# 05_USB.net
KiCad netlist of a schematic drawn in Altium Designer
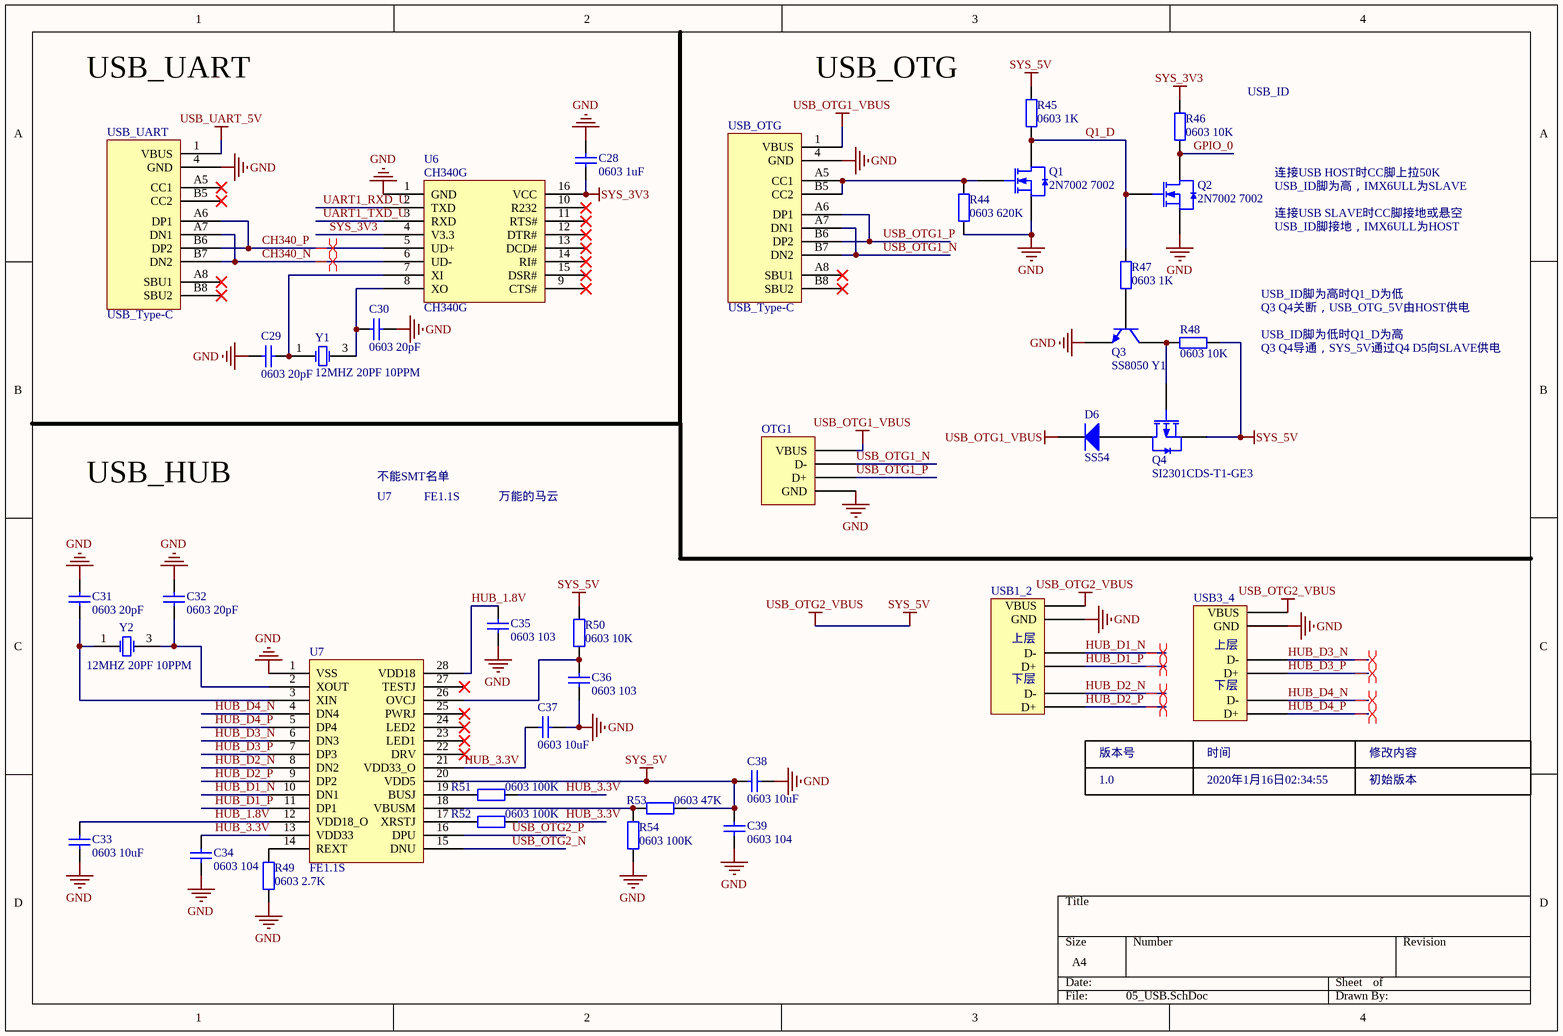
[diagram p0: 05_USB.SchDoc]

(export (version "E")
  (design (tool "Eeschema 10.0.6"))
  (components
    (comp (ref "C28")
      (value "0603 1uF")
      (footprint "LC-0603_C")
      (description "贴片电容")
      (libsource (lib "JLC") (part "0603 1.5nF (152) 10% 50V"))
    )
    (comp (ref "C29")
      (value "0603 20pF")
      (footprint "LC-0603_C")
      (description "贴片电容")
      (libsource (lib "JLC") (part "0603 1.5nF (152) 10% 50V"))
    )
    (comp (ref "C30")
      (value "0603 20pF")
      (footprint "LC-0603_C")
      (description "贴片电容")
      (libsource (lib "JLC") (part "0603 1.5nF (152) 10% 50V"))
    )
    (comp (ref "C31")
      (value "0603 20pF")
      (footprint "LC-0603_C")
      (description "贴片电容")
      (libsource (lib "JLC") (part "0603 1.5nF (152) 10% 50V"))
    )
    (comp (ref "C32")
      (value "0603 20pF")
      (footprint "LC-0603_C")
      (description "贴片电容")
      (libsource (lib "JLC") (part "0603 1.5nF (152) 10% 50V"))
    )
    (comp (ref "C33")
      (value "0603 10uF")
      (footprint "LC-0603_C")
      (description "贴片电容")
      (libsource (lib "JLC") (part "0603 1.5nF (152) 10% 50V"))
    )
    (comp (ref "C34")
      (value "0603 104")
      (footprint "LC-0603_C")
      (description "贴片电容")
      (libsource (lib "JLC") (part "0603 1.5nF (152) 10% 50V"))
    )
    (comp (ref "C35")
      (value "0603 103")
      (footprint "LC-0603_C")
      (description "贴片电容")
      (libsource (lib "JLC") (part "0603 1.5nF (152) 10% 50V"))
    )
    (comp (ref "C36")
      (value "0603 103")
      (footprint "LC-0603_C")
      (description "贴片电容")
      (libsource (lib "JLC") (part "0603 1.5nF (152) 10% 50V"))
    )
    (comp (ref "C37")
      (value "0603 10uF")
      (footprint "LC-0603_C")
      (description "贴片电容")
      (libsource (lib "JLC") (part "0603 1.5nF (152) 10% 50V"))
    )
    (comp (ref "C38")
      (value "0603 10uF")
      (footprint "LC-0603_C")
      (description "贴片电容")
      (libsource (lib "JLC") (part "0603 1.5nF (152) 10% 50V"))
    )
    (comp (ref "C39")
      (value "0603 104")
      (footprint "LC-0603_C")
      (description "贴片电容")
      (libsource (lib "JLC") (part "0603 1.5nF (152) 10% 50V"))
    )
    (comp (ref "D6")
      (value "SS54")
      (footprint "LC-SMA(DO-214AC)_S1")
      (description "二极管")
      (libsource (lib "JLC") (part "SMA(DO-214AC) SS54"))
    )
    (comp (ref "OTG1")
      (value "~")
      (footprint "USB插座_侧插")
      (libsource (lib "Integrated_Library2") (part "USB_插座"))
    )
    (comp (ref "Q1")
      (value "2N7002 7002")
      (footprint "LC-SOT-23(SOT-23-3)")
      (description "MOS(场效应管)")
      (libsource (lib "JLC") (part "2N7002 7002"))
    )
    (comp (ref "Q2")
      (value "2N7002 7002")
      (footprint "LC-SOT-23(SOT-23-3)")
      (description "MOS(场效应管)")
      (libsource (lib "JLC") (part "2N7002 7002"))
    )
    (comp (ref "Q3")
      (value "SS8050 Y1")
      (footprint "LC-SOT-23(SOT-23-3)")
      (description "三极管")
      (libsource (lib "JLC") (part "SOT-23 SS8050 Y1"))
    )
    (comp (ref "Q4")
      (value "SI2301CDS-T1-GE3")
      (footprint "LC-SOT-23(SOT-23-3)")
      (description "MOS(场效应管)")
      (libsource (lib "JLC") (part "SI2301CDS-T1-GE3"))
    )
    (comp (ref "R44")
      (value "0603 620K")
      (footprint "LC-0603_R")
      (description "贴片电阻")
      (libsource (lib "JLC") (part "0603 1.1KΩ (1101) 1%"))
    )
    (comp (ref "R45")
      (value "0603 1K")
      (footprint "LC-0603_R")
      (description "贴片电阻")
      (libsource (lib "JLC") (part "0603 1.1KΩ (1101) 1%"))
    )
    (comp (ref "R46")
      (value "0603 10K")
      (footprint "LC-0603_R")
      (description "贴片电阻")
      (libsource (lib "JLC") (part "0603 1.1KΩ (1101) 1%"))
    )
    (comp (ref "R47")
      (value "0603 1K")
      (footprint "LC-0603_R")
      (description "贴片电阻")
      (libsource (lib "JLC") (part "0603 1.1KΩ (1101) 1%"))
    )
    (comp (ref "R48")
      (value "0603 10K")
      (footprint "LC-0603_R")
      (description "贴片电阻")
      (libsource (lib "") (part "0603 1.1KΩ (1101) 1%_2"))
    )
    (comp (ref "R49")
      (value "0603 2.7K")
      (footprint "LC-0603_R")
      (description "贴片电阻")
      (libsource (lib "JLC") (part "0603 1.1KΩ (1101) 1%"))
    )
    (comp (ref "R50")
      (value "0603 10K")
      (footprint "LC-0603_R")
      (description "贴片电阻")
      (libsource (lib "JLC") (part "0603 1.1KΩ (1101) 1%"))
    )
    (comp (ref "R51")
      (value "0603 100K")
      (footprint "LC-0603_R")
      (description "贴片电阻")
      (libsource (lib "") (part "0603 1.1KΩ (1101) 1%_2"))
    )
    (comp (ref "R52")
      (value "0603 100K")
      (footprint "LC-0603_R")
      (description "贴片电阻")
      (libsource (lib "") (part "0603 1.1KΩ (1101) 1%_2"))
    )
    (comp (ref "R53")
      (value "0603 47K")
      (footprint "LC-0603_R")
      (description "贴片电阻")
      (libsource (lib "") (part "0603 1.1KΩ (1101) 1%_2"))
    )
    (comp (ref "R54")
      (value "0603 100K")
      (footprint "LC-0603_R")
      (description "贴片电阻")
      (libsource (lib "") (part "0603 1.1KΩ (1101) 1%_1"))
    )
    (comp (ref "U6")
      (value "CH340G")
      (footprint "LC-SOIC-16_150mil")
      (description "USB")
      (libsource (lib "JLC") (part "CH340G"))
    )
    (comp (ref "U7")
      (value "FE1.1S")
      (footprint "LC-SSOP-28_150mil")
      (libsource (lib "Integrated_Library2") (part "FE1.1S"))
    )
    (comp (ref "USB1_2")
      (value "~")
      (footprint "USB插座_双层")
      (libsource (lib "Integrated_Library2") (part "USB双层插座"))
    )
    (comp (ref "USB3_4")
      (value "~")
      (footprint "USB插座_双层")
      (libsource (lib "Integrated_Library2") (part "USB双层插座"))
    )
    (comp (ref "USB_OTG")
      (value "USB_Type-C")
      (footprint "Type-C 16P")
      (libsource (lib "Integrated_Library2") (part "USB_Type-C"))
    )
    (comp (ref "USB_UART")
      (value "USB_Type-C")
      (footprint "Type-C 16P")
      (libsource (lib "Integrated_Library2") (part "USB_Type-C"))
    )
    (comp (ref "Y1")
      (value "12MHZ 20PF 10PPM")
      (footprint "LC-SMD-3225_4P")
      (description "贴片晶振")
      (libsource (lib "JLC") (part "SMD-3225_4P  12MHZ 20PF 10PPM"))
    )
    (comp (ref "Y2")
      (value "12MHZ 20PF 10PPM")
      (footprint "LC-SMD-3225_4P")
      (description "贴片晶振")
      (libsource (lib "JLC") (part "SMD-3225_4P  12MHZ 20PF 10PPM"))
    )
  )
  (nets
    (net (code "1") (name "/CH340_N") (class "Default")
      (node (ref "U6") (pin "6") (pinfunction "UD-_6") (pintype "passive"))
      (node (ref "USB_UART") (pin "A7") (pinfunction "DN1_A7") (pintype "passive"))
      (node (ref "USB_UART") (pin "B7") (pinfunction "DN2_B7") (pintype "passive"))
    )
    (net (code "2") (name "/CH340_P") (class "Default")
      (node (ref "U6") (pin "5") (pinfunction "UD+_5") (pintype "passive"))
      (node (ref "USB_UART") (pin "A6") (pinfunction "DP1_A6") (pintype "passive"))
      (node (ref "USB_UART") (pin "B6") (pinfunction "DP2_B6") (pintype "passive"))
    )
    (net (code "3") (name "/GPIO_0") (class "Default")
      (node (ref "Q2") (pin "3") (pinfunction "D_3") (pintype "passive"))
      (node (ref "R46") (pin "1") (pinfunction "1_1") (pintype "passive"))
    )
    (net (code "4") (name "/HUB_1.8V") (class "Default")
      (node (ref "C33") (pin "1") (pinfunction "1_1") (pintype "passive"))
      (node (ref "C35") (pin "1") (pinfunction "1_1") (pintype "passive"))
      (node (ref "U7") (pin "12") (pinfunction "VDD18_O_12") (pintype "passive"))
      (node (ref "U7") (pin "28") (pinfunction "VDD18_28") (pintype "passive"))
    )
    (net (code "5") (name "/HUB_3.3V") (class "Default")
      (node (ref "C34") (pin "1") (pinfunction "1_1") (pintype "passive"))
      (node (ref "C37") (pin "1") (pinfunction "1_1") (pintype "passive"))
      (node (ref "R51") (pin "1") (pinfunction "1_1") (pintype "passive"))
      (node (ref "R52") (pin "1") (pinfunction "1_1") (pintype "passive"))
      (node (ref "U7") (pin "13") (pinfunction "VDD33_13") (pintype "passive"))
      (node (ref "U7") (pin "21") (pinfunction "VDD33_O_21") (pintype "passive"))
    )
    (net (code "6") (name "/HUB_D1_N") (class "Default")
      (node (ref "U7") (pin "10") (pinfunction "DN1_10") (pintype "passive"))
      (node (ref "USB1_2") (pin "2") (pinfunction "D-_2") (pintype "passive"))
    )
    (net (code "7") (name "/HUB_D1_P") (class "Default")
      (node (ref "U7") (pin "11") (pinfunction "DP1_11") (pintype "passive"))
      (node (ref "USB1_2") (pin "1") (pinfunction "D+_1") (pintype "passive"))
    )
    (net (code "8") (name "/HUB_D2_N") (class "Default")
      (node (ref "U7") (pin "8") (pinfunction "DN2_8") (pintype "passive"))
      (node (ref "USB1_2") (pin "5") (pinfunction "D-_5") (pintype "passive"))
    )
    (net (code "9") (name "/HUB_D2_P") (class "Default")
      (node (ref "U7") (pin "9") (pinfunction "DP2_9") (pintype "passive"))
      (node (ref "USB1_2") (pin "4") (pinfunction "D+_4") (pintype "passive"))
    )
    (net (code "10") (name "/HUB_D3_N") (class "Default")
      (node (ref "U7") (pin "6") (pinfunction "DN3_6") (pintype "passive"))
      (node (ref "USB3_4") (pin "2") (pinfunction "D-_2") (pintype "passive"))
    )
    (net (code "11") (name "/HUB_D3_P") (class "Default")
      (node (ref "U7") (pin "7") (pinfunction "DP3_7") (pintype "passive"))
      (node (ref "USB3_4") (pin "1") (pinfunction "D+_1") (pintype "passive"))
    )
    (net (code "12") (name "/HUB_D4_N") (class "Default")
      (node (ref "U7") (pin "4") (pinfunction "DN4_4") (pintype "passive"))
      (node (ref "USB3_4") (pin "5") (pinfunction "D-_5") (pintype "passive"))
    )
    (net (code "13") (name "/HUB_D4_P") (class "Default")
      (node (ref "U7") (pin "5") (pinfunction "DP4_5") (pintype "passive"))
      (node (ref "USB3_4") (pin "4") (pinfunction "D+_4") (pintype "passive"))
    )
    (net (code "14") (name "/Q1_D") (class "Default")
      (node (ref "Q1") (pin "3") (pinfunction "D_3") (pintype "passive"))
      (node (ref "Q2") (pin "1") (pinfunction "G_1") (pintype "passive"))
      (node (ref "R45") (pin "1") (pinfunction "1_1") (pintype "passive"))
      (node (ref "R47") (pin "2") (pinfunction "2_2") (pintype "passive"))
    )
    (net (code "15") (name "/UART1_RXD_U") (class "Default")
      (node (ref "U6") (pin "2") (pinfunction "TXD_2") (pintype "passive"))
    )
    (net (code "16") (name "/UART1_TXD_U") (class "Default")
      (node (ref "U6") (pin "3") (pinfunction "RXD_3") (pintype "passive"))
    )
    (net (code "17") (name "/USB_OTG1_N") (class "Default")
      (node (ref "OTG1") (pin "2") (pinfunction "D-_2") (pintype "passive"))
      (node (ref "USB_OTG") (pin "A7") (pinfunction "DN1_A7") (pintype "passive"))
      (node (ref "USB_OTG") (pin "B7") (pinfunction "DN2_B7") (pintype "passive"))
    )
    (net (code "18") (name "/USB_OTG1_P") (class "Default")
      (node (ref "OTG1") (pin "1") (pinfunction "D+_1") (pintype "passive"))
      (node (ref "USB_OTG") (pin "A6") (pinfunction "DP1_A6") (pintype "passive"))
      (node (ref "USB_OTG") (pin "B6") (pinfunction "DP2_B6") (pintype "passive"))
    )
    (net (code "19") (name "/USB_OTG2_N") (class "Default")
      (node (ref "U7") (pin "15") (pinfunction "DNU_15") (pintype "passive"))
    )
    (net (code "20") (name "/USB_OTG2_P") (class "Default")
      (node (ref "U7") (pin "16") (pinfunction "DPU_16") (pintype "passive"))
    )
    (net (code "21") (name "GND") (class "Default")
      (node (ref "C28") (pin "2") (pinfunction "2_2") (pintype "passive"))
      (node (ref "C29") (pin "2") (pinfunction "2_2") (pintype "passive"))
      (node (ref "C30") (pin "1") (pinfunction "1_1") (pintype "passive"))
      (node (ref "C31") (pin "1") (pinfunction "1_1") (pintype "passive"))
      (node (ref "C32") (pin "1") (pinfunction "1_1") (pintype "passive"))
      (node (ref "C33") (pin "2") (pinfunction "2_2") (pintype "passive"))
      (node (ref "C34") (pin "2") (pinfunction "2_2") (pintype "passive"))
      (node (ref "C35") (pin "2") (pinfunction "2_2") (pintype "passive"))
      (node (ref "C36") (pin "2") (pinfunction "2_2") (pintype "passive"))
      (node (ref "C37") (pin "2") (pinfunction "2_2") (pintype "passive"))
      (node (ref "C38") (pin "1") (pinfunction "1_1") (pintype "passive"))
      (node (ref "C39") (pin "2") (pinfunction "2_2") (pintype "passive"))
      (node (ref "OTG1") (pin "0") (pinfunction "GND_0") (pintype "passive"))
      (node (ref "Q1") (pin "2") (pinfunction "S_2") (pintype "passive"))
      (node (ref "Q2") (pin "2") (pinfunction "S_2") (pintype "passive"))
      (node (ref "Q3") (pin "2") (pinfunction "E_2") (pintype "passive"))
      (node (ref "R44") (pin "1") (pinfunction "1_1") (pintype "passive"))
      (node (ref "R49") (pin "1") (pinfunction "1_1") (pintype "passive"))
      (node (ref "R54") (pin "2") (pinfunction "2_2") (pintype "passive"))
      (node (ref "U6") (pin "1") (pinfunction "GND_1") (pintype "passive"))
      (node (ref "U7") (pin "1") (pinfunction "VSS_1") (pintype "passive"))
      (node (ref "USB1_2") (pin "0") (pinfunction "GND_0") (pintype "passive"))
      (node (ref "USB3_4") (pin "0") (pinfunction "GND_0") (pintype "passive"))
      (node (ref "USB_OTG") (pin "4") (pinfunction "GND_4") (pintype "passive"))
      (node (ref "USB_UART") (pin "4") (pinfunction "GND_4") (pintype "passive"))
    )
    (net (code "22") (name "Net-(D6-A)") (class "Default")
      (node (ref "D6") (pin "1") (pinfunction "A_1") (pintype "passive"))
      (node (ref "Q4") (pin "3") (pinfunction "D_3") (pintype "passive"))
    )
    (net (code "23") (name "Net-(Q1-G)") (class "Default")
      (node (ref "Q1") (pin "1") (pinfunction "G_1") (pintype "passive"))
      (node (ref "R44") (pin "2") (pinfunction "2_2") (pintype "passive"))
      (node (ref "USB_OTG") (pin "A5") (pinfunction "CC1_A5") (pintype "passive"))
      (node (ref "USB_OTG") (pin "B5") (pinfunction "CC2_B5") (pintype "passive"))
    )
    (net (code "24") (name "Net-(Q3-B)") (class "Default")
      (node (ref "Q3") (pin "1") (pinfunction "B_1") (pintype "passive"))
      (node (ref "R47") (pin "1") (pinfunction "1_1") (pintype "passive"))
    )
    (net (code "25") (name "Net-(Q3-C)") (class "Default")
      (node (ref "Q3") (pin "3") (pinfunction "C_3") (pintype "passive"))
      (node (ref "Q4") (pin "1") (pinfunction "G_1") (pintype "passive"))
      (node (ref "R48") (pin "2") (pinfunction "2_2") (pintype "passive"))
    )
    (net (code "26") (name "Net-(U6-XI)") (class "Default")
      (node (ref "C29") (pin "1") (pinfunction "1_1") (pintype "passive"))
      (node (ref "U6") (pin "7") (pinfunction "XI_7") (pintype "passive"))
      (node (ref "Y1") (pin "1") (pinfunction "OSC1_1") (pintype "passive"))
    )
    (net (code "27") (name "Net-(U6-XO)") (class "Default")
      (node (ref "C30") (pin "2") (pinfunction "2_2") (pintype "passive"))
      (node (ref "U6") (pin "8") (pinfunction "XO_8") (pintype "passive"))
      (node (ref "Y1") (pin "3") (pinfunction "OSC2_3") (pintype "passive"))
    )
    (net (code "28") (name "Net-(U7-BUSJ)") (class "Default")
      (node (ref "R51") (pin "2") (pinfunction "2_2") (pintype "passive"))
      (node (ref "U7") (pin "19") (pinfunction "BUSJ_19") (pintype "passive"))
    )
    (net (code "29") (name "Net-(U7-OVCJ)") (class "Default")
      (node (ref "C36") (pin "1") (pinfunction "1_1") (pintype "passive"))
      (node (ref "R50") (pin "1") (pinfunction "1_1") (pintype "passive"))
      (node (ref "U7") (pin "26") (pinfunction "OVCJ_26") (pintype "passive"))
    )
    (net (code "30") (name "Net-(U7-REXT)") (class "Default")
      (node (ref "R49") (pin "2") (pinfunction "2_2") (pintype "passive"))
      (node (ref "U7") (pin "14") (pinfunction "REXT_14") (pintype "passive"))
    )
    (net (code "31") (name "Net-(U7-VBUSM)") (class "Default")
      (node (ref "R53") (pin "2") (pinfunction "2_2") (pintype "passive"))
      (node (ref "R54") (pin "1") (pinfunction "1_1") (pintype "passive"))
      (node (ref "U7") (pin "18") (pinfunction "VBUSM_18") (pintype "passive"))
    )
    (net (code "32") (name "Net-(U7-XIN)") (class "Default")
      (node (ref "C31") (pin "2") (pinfunction "2_2") (pintype "passive"))
      (node (ref "U7") (pin "3") (pinfunction "XIN_3") (pintype "passive"))
      (node (ref "Y2") (pin "1") (pinfunction "OSC1_1") (pintype "passive"))
    )
    (net (code "33") (name "Net-(U7-XOUT)") (class "Default")
      (node (ref "C32") (pin "2") (pinfunction "2_2") (pintype "passive"))
      (node (ref "U7") (pin "2") (pinfunction "XOUT_2") (pintype "passive"))
      (node (ref "Y2") (pin "3") (pinfunction "OSC2_3") (pintype "passive"))
    )
    (net (code "34") (name "Net-(U7-XRSTJ)") (class "Default")
      (node (ref "R52") (pin "2") (pinfunction "2_2") (pintype "passive"))
      (node (ref "U7") (pin "17") (pinfunction "XRSTJ_17") (pintype "passive"))
    )
    (net (code "35") (name "SYS_3V3") (class "Default")
      (node (ref "C28") (pin "1") (pinfunction "1_1") (pintype "passive"))
      (node (ref "R46") (pin "2") (pinfunction "2_2") (pintype "passive"))
      (node (ref "U6") (pin "16") (pinfunction "VCC_16") (pintype "passive"))
      (node (ref "U6") (pin "4") (pinfunction "V3.3_4") (pintype "passive"))
    )
    (net (code "36") (name "SYS_5V") (class "Default")
      (node (ref "C38") (pin "2") (pinfunction "2_2") (pintype "passive"))
      (node (ref "C39") (pin "1") (pinfunction "1_1") (pintype "passive"))
      (node (ref "Q4") (pin "2") (pinfunction "S_2") (pintype "passive"))
      (node (ref "R45") (pin "2") (pinfunction "2_2") (pintype "passive"))
      (node (ref "R48") (pin "1") (pinfunction "1_1") (pintype "passive"))
      (node (ref "R50") (pin "2") (pinfunction "2_2") (pintype "passive"))
      (node (ref "R53") (pin "1") (pinfunction "1_1") (pintype "passive"))
      (node (ref "U7") (pin "20") (pinfunction "VDD5_20") (pintype "passive"))
      (node (ref "USB1_2") (pin "3") (pinfunction "VBUS_3") (pintype "passive"))
      (node (ref "USB3_4") (pin "3") (pinfunction "VBUS_3") (pintype "passive"))
    )
    (net (code "37") (name "USB_OTG1_VBUS") (class "Default")
      (node (ref "D6") (pin "2") (pinfunction "K_2") (pintype "passive"))
      (node (ref "OTG1") (pin "3") (pinfunction "VBUS_3") (pintype "passive"))
      (node (ref "USB_OTG") (pin "1") (pinfunction "VBUS_1") (pintype "passive"))
    )
    (net (code "38") (name "USB_UART_5V") (class "Default")
      (node (ref "USB_UART") (pin "1") (pinfunction "VBUS_1") (pintype "passive"))
    )
    (net (code "39") (name "unconnected-(U6-CTS#-Pad9)") (class "Default")
      (node (ref "U6") (pin "9") (pinfunction "CTS#_9") (pintype "passive+no_connect"))
    )
    (net (code "40") (name "unconnected-(U6-DCD#-Pad13)") (class "Default")
      (node (ref "U6") (pin "13") (pinfunction "DCD#_13") (pintype "passive+no_connect"))
    )
    (net (code "41") (name "unconnected-(U6-DSR#-Pad15)") (class "Default")
      (node (ref "U6") (pin "15") (pinfunction "DSR#_15") (pintype "passive+no_connect"))
    )
    (net (code "42") (name "unconnected-(U6-DTR#-Pad12)") (class "Default")
      (node (ref "U6") (pin "12") (pinfunction "DTR#_12") (pintype "passive+no_connect"))
    )
    (net (code "43") (name "unconnected-(U6-R232-Pad10)") (class "Default")
      (node (ref "U6") (pin "10") (pinfunction "R232_10") (pintype "passive+no_connect"))
    )
    (net (code "44") (name "unconnected-(U6-RI#-Pad14)") (class "Default")
      (node (ref "U6") (pin "14") (pinfunction "RI#_14") (pintype "passive+no_connect"))
    )
    (net (code "45") (name "unconnected-(U6-RTS#-Pad11)") (class "Default")
      (node (ref "U6") (pin "11") (pinfunction "RTS#_11") (pintype "passive+no_connect"))
    )
    (net (code "46") (name "unconnected-(U7-DRV-Pad22)") (class "Default")
      (node (ref "U7") (pin "22") (pinfunction "DRV_22") (pintype "passive+no_connect"))
    )
    (net (code "47") (name "unconnected-(U7-LED1-Pad23)") (class "Default")
      (node (ref "U7") (pin "23") (pinfunction "LED1_23") (pintype "passive+no_connect"))
    )
    (net (code "48") (name "unconnected-(U7-LED2-Pad24)") (class "Default")
      (node (ref "U7") (pin "24") (pinfunction "LED2_24") (pintype "passive+no_connect"))
    )
    (net (code "49") (name "unconnected-(U7-PWRJ-Pad25)") (class "Default")
      (node (ref "U7") (pin "25") (pinfunction "PWRJ_25") (pintype "passive+no_connect"))
    )
    (net (code "50") (name "unconnected-(U7-TESTJ-Pad27)") (class "Default")
      (node (ref "U7") (pin "27") (pinfunction "TESTJ_27") (pintype "passive+no_connect"))
    )
    (net (code "51") (name "unconnected-(USB_OTG-SBU1-PadA8)") (class "Default")
      (node (ref "USB_OTG") (pin "A8") (pinfunction "SBU1_A8") (pintype "passive+no_connect"))
    )
    (net (code "52") (name "unconnected-(USB_OTG-SBU2-PadB8)") (class "Default")
      (node (ref "USB_OTG") (pin "B8") (pinfunction "SBU2_B8") (pintype "passive+no_connect"))
    )
    (net (code "53") (name "unconnected-(USB_UART-CC1-PadA5)") (class "Default")
      (node (ref "USB_UART") (pin "A5") (pinfunction "CC1_A5") (pintype "passive+no_connect"))
    )
    (net (code "54") (name "unconnected-(USB_UART-CC2-PadB5)") (class "Default")
      (node (ref "USB_UART") (pin "B5") (pinfunction "CC2_B5") (pintype "passive+no_connect"))
    )
    (net (code "55") (name "unconnected-(USB_UART-SBU1-PadA8)") (class "Default")
      (node (ref "USB_UART") (pin "A8") (pinfunction "SBU1_A8") (pintype "passive+no_connect"))
    )
    (net (code "56") (name "unconnected-(USB_UART-SBU2-PadB8)") (class "Default")
      (node (ref "USB_UART") (pin "B8") (pinfunction "SBU2_B8") (pintype "passive+no_connect"))
    )
  )
)
